# PET_Diag_Clip.net
KiCad netlist of a schematic drawn in EAGLE
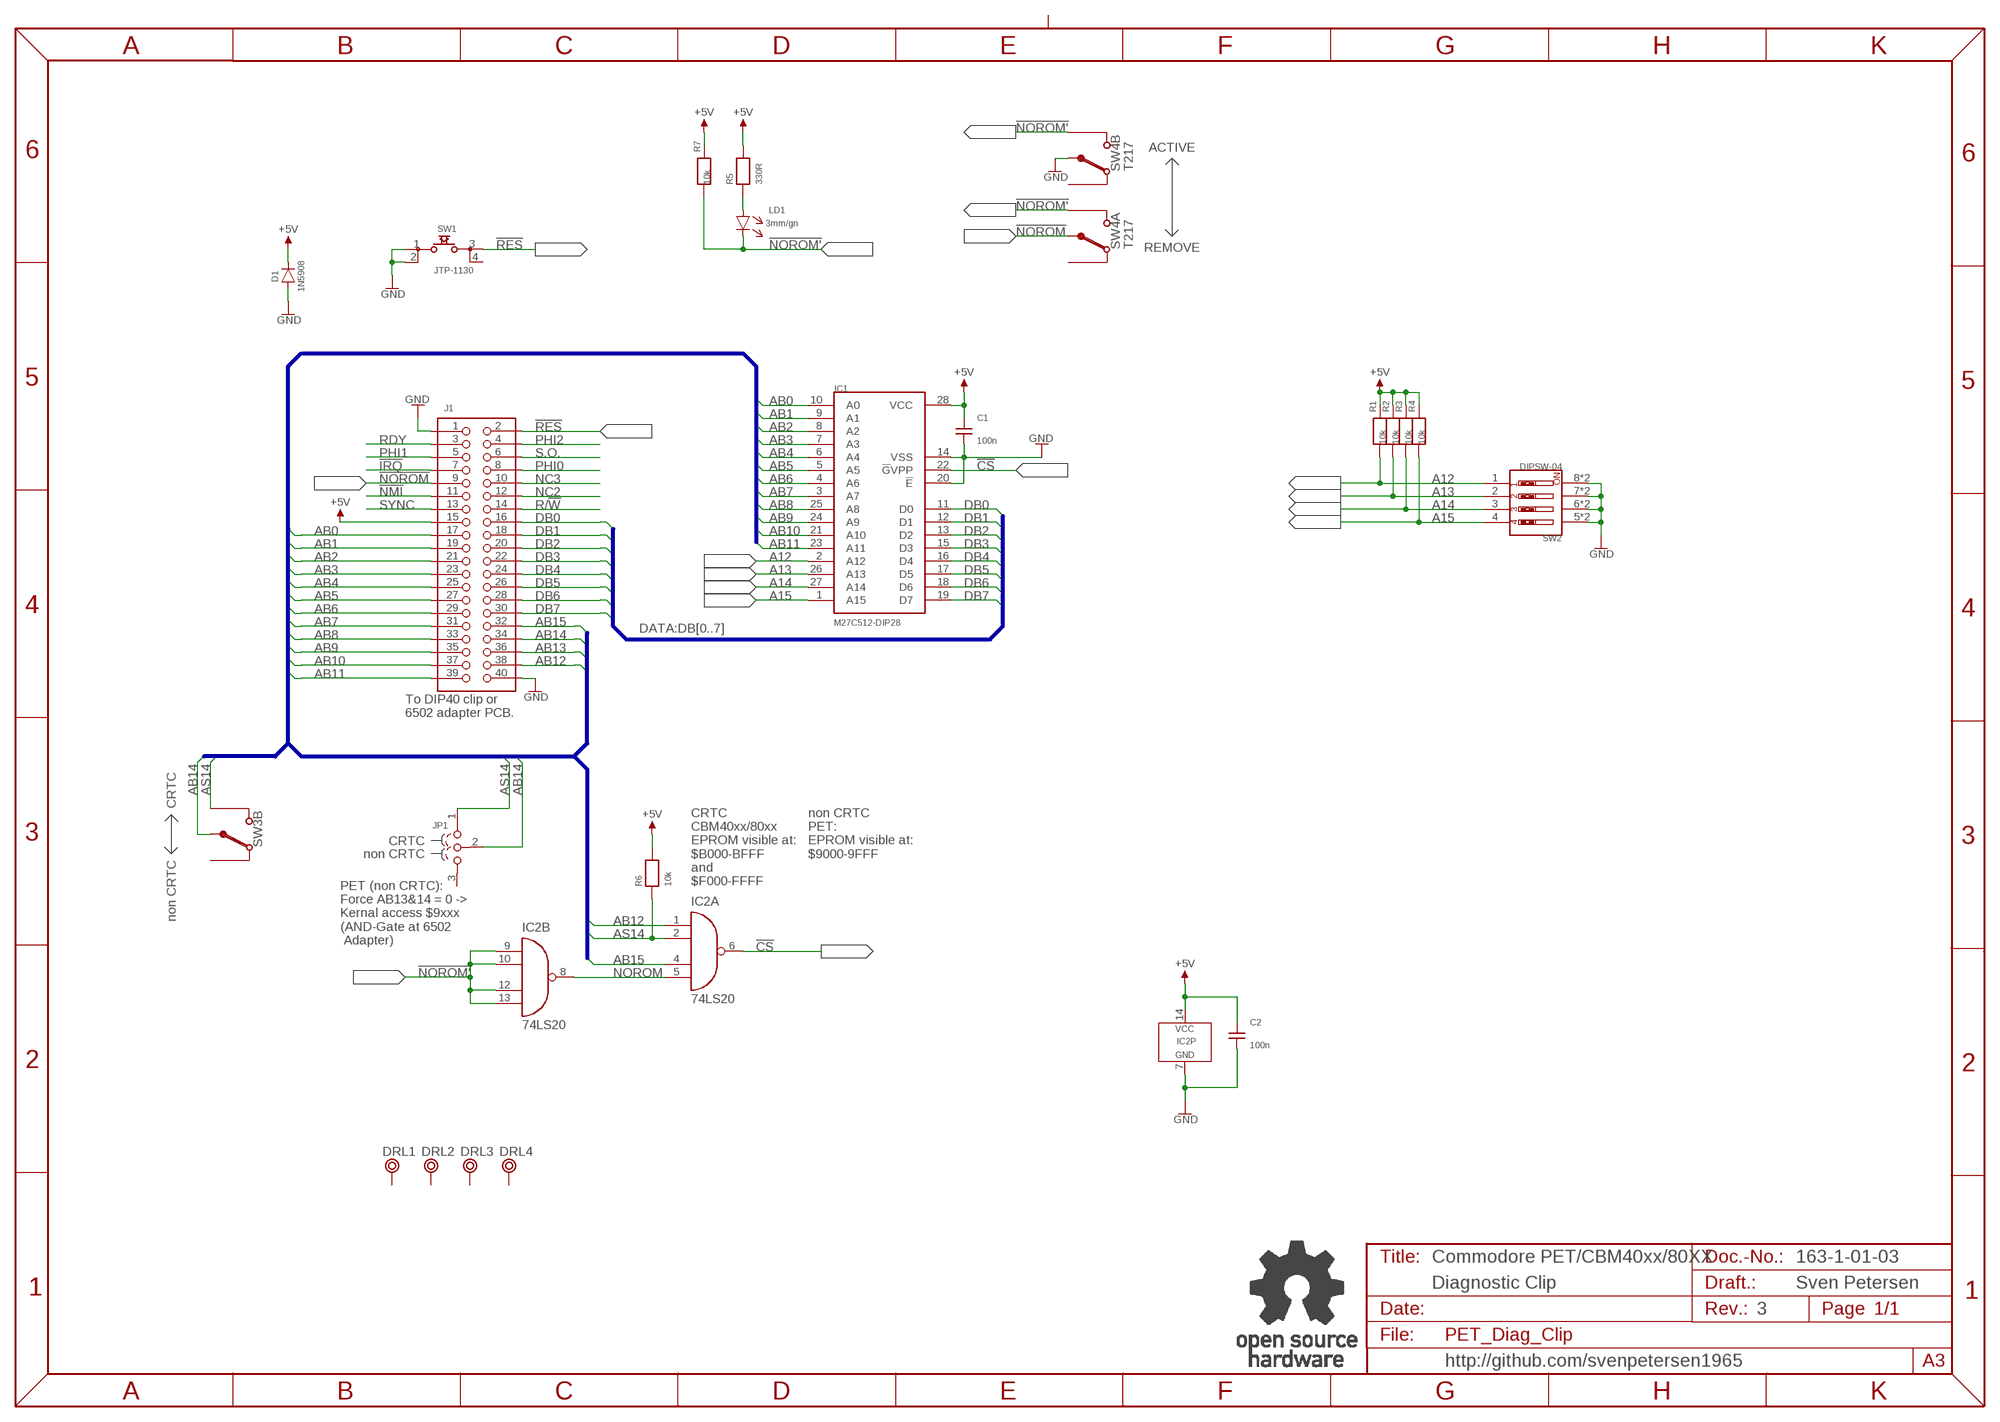
[diagram p0: schematic, sheet 1]

(export (version "E")
  (design (tool "Eeschema 10.0.6"))
  (components
    (comp (ref "C1")
      (value "100n")
      (footprint "eagle-import:C-2,5")
      (libsource (lib "eagle-import") (part "CAP01"))
    )
    (comp (ref "C2")
      (value "100n")
      (footprint "eagle-import:C-2,5")
      (libsource (lib "eagle-import") (part "CAP01"))
    )
    (comp (ref "D1")
      (value "1N5908")
      (footprint "eagle-import:DO-201")
      (libsource (lib "eagle-import") (part "1N5402"))
    )
    (comp (ref "DRL1")
      (value "BOHR3,5")
      (footprint "eagle-import:BOHR3,5")
      (libsource (lib "eagle-import") (part "BOHR3,5"))
    )
    (comp (ref "DRL2")
      (value "BOHR3,5")
      (footprint "eagle-import:BOHR3,5")
      (libsource (lib "eagle-import") (part "BOHR3,5"))
    )
    (comp (ref "DRL3")
      (value "BOHR3,5")
      (footprint "eagle-import:BOHR3,5")
      (libsource (lib "eagle-import") (part "BOHR3,5"))
    )
    (comp (ref "DRL4")
      (value "BOHR3,5")
      (footprint "eagle-import:BOHR3,5")
      (libsource (lib "eagle-import") (part "BOHR3,5"))
    )
    (comp (ref "IC1")
      (value "M27C512-DIP28")
      (footprint "eagle-import:DIL28-6")
      (libsource (lib "eagle-import") (part "M27C512-DIP28"))
    )
    (comp (ref "IC2")
      (value "74LS20")
      (footprint "eagle-import:DIL-14")
      (libsource (lib "eagle-import") (part "7420N"))
    )
    (comp (ref "J1")
      (value "PINHD-2X20WV")
      (footprint "eagle-import:2X20WV")
      (libsource (lib "eagle-import") (part "PINHD-2X20WV"))
    )
    (comp (ref "JP1")
      (value "COMBI-3P")
      (footprint "eagle-import:COMBI-3P")
      (libsource (lib "eagle-import") (part "COMBI-3P"))
    )
    (comp (ref "LD1")
      (value "3mm/gn")
      (footprint "eagle-import:3MM")
      (libsource (lib "eagle-import") (part "3MM"))
    )
    (comp (ref "R1")
      (value "10k")
      (footprint "eagle-import:R-10")
      (libsource (lib "eagle-import") (part "RES04"))
    )
    (comp (ref "R2")
      (value "10k")
      (footprint "eagle-import:R-10")
      (libsource (lib "eagle-import") (part "RES04"))
    )
    (comp (ref "R3")
      (value "10k")
      (footprint "eagle-import:R-10")
      (libsource (lib "eagle-import") (part "RES04"))
    )
    (comp (ref "R4")
      (value "10k")
      (footprint "eagle-import:R-10")
      (libsource (lib "eagle-import") (part "RES04"))
    )
    (comp (ref "R5")
      (value "330R")
      (footprint "eagle-import:R-10")
      (libsource (lib "eagle-import") (part "RES04"))
    )
    (comp (ref "R6")
      (value "10k")
      (footprint "eagle-import:R-10")
      (libsource (lib "eagle-import") (part "RES04"))
    )
    (comp (ref "R7")
      (value "10k")
      (footprint "eagle-import:R-10")
      (libsource (lib "eagle-import") (part "RES04"))
    )
    (comp (ref "SW1")
      (value "JTP-1130")
      (footprint "eagle-import:JTP-1130")
      (libsource (lib "eagle-import") (part "JTP-1130"))
    )
    (comp (ref "SW2")
      (value "DIPSW-04")
      (footprint "eagle-import:DIPSW-04V-COMBI")
      (libsource (lib "eagle-import") (part "DIPSW-04"))
    )
    (comp (ref "SW3")
      (value "MSS22D18")
      (footprint "eagle-import:DPDT_9MM")
      (libsource (lib "eagle-import") (part "DPDT_9MM"))
    )
    (comp (ref "SW4")
      (value "T217")
      (footprint "eagle-import:T217_SIDE")
      (libsource (lib "eagle-import") (part "T217"))
    )
    (comp (ref "U$13")
      (value "OPEN_SOURCE_HW")
      (footprint "eagle-import:OPENHW")
      (libsource (lib "eagle-import") (part "OPEN_SOURCE_HW"))
    )
  )
  (nets
    (net (code "9") (name "+5V") (class "Default")
      (node (ref "C1") (pin "2") (pinfunction "2_2") (pintype "passive"))
      (node (ref "C2") (pin "2") (pinfunction "2_2") (pintype "passive"))
      (node (ref "D1") (pin "K") (pinfunction "K_K") (pintype "passive"))
      (node (ref "IC1") (pin "28") (pinfunction "VCC_28") (pintype "power_in"))
      (node (ref "IC2") (pin "14") (pinfunction "VCC_14") (pintype "bidirectional"))
      (node (ref "J1") (pin "15") (pinfunction "15_15") (pintype "passive"))
      (node (ref "R1") (pin "1") (pinfunction "1_1") (pintype "passive"))
      (node (ref "R2") (pin "1") (pinfunction "1_1") (pintype "passive"))
      (node (ref "R3") (pin "1") (pinfunction "1_1") (pintype "passive"))
      (node (ref "R4") (pin "1") (pinfunction "1_1") (pintype "passive"))
      (node (ref "R5") (pin "2") (pinfunction "2_2") (pintype "passive"))
      (node (ref "R6") (pin "2") (pinfunction "2_2") (pintype "passive"))
      (node (ref "R7") (pin "1") (pinfunction "1_1") (pintype "passive"))
    )
    (net (code "10") (name "/A12") (class "Default")
      (node (ref "IC1") (pin "2") (pinfunction "A12_2") (pintype "input"))
      (node (ref "R1") (pin "2") (pinfunction "2_2") (pintype "passive"))
      (node (ref "SW2") (pin "1") (pinfunction "1_1") (pintype "passive"))
    )
    (net (code "11") (name "/A13") (class "Default")
      (node (ref "IC1") (pin "26") (pinfunction "A13_26") (pintype "input"))
      (node (ref "R2") (pin "2") (pinfunction "2_2") (pintype "passive"))
      (node (ref "SW2") (pin "2") (pinfunction "2_2") (pintype "passive"))
    )
    (net (code "12") (name "/A14") (class "Default")
      (node (ref "IC1") (pin "27") (pinfunction "A14_27") (pintype "input"))
      (node (ref "R3") (pin "2") (pinfunction "2_2") (pintype "passive"))
      (node (ref "SW2") (pin "3") (pinfunction "3_3") (pintype "passive"))
    )
    (net (code "13") (name "/A15") (class "Default")
      (node (ref "IC1") (pin "1") (pinfunction "A15_1") (pintype "input"))
      (node (ref "R4") (pin "2") (pinfunction "2_2") (pintype "passive"))
      (node (ref "SW2") (pin "4") (pinfunction "4_4") (pintype "passive"))
    )
    (net (code "14") (name "/AB0") (class "Default")
      (node (ref "IC1") (pin "10") (pinfunction "A0_10") (pintype "input"))
      (node (ref "J1") (pin "17") (pinfunction "17_17") (pintype "passive"))
    )
    (net (code "15") (name "/AB1") (class "Default")
      (node (ref "IC1") (pin "9") (pinfunction "A1_9") (pintype "input"))
      (node (ref "J1") (pin "19") (pinfunction "19_19") (pintype "passive"))
    )
    (net (code "16") (name "/AB2") (class "Default")
      (node (ref "IC1") (pin "8") (pinfunction "A2_8") (pintype "input"))
      (node (ref "J1") (pin "21") (pinfunction "21_21") (pintype "passive"))
    )
    (net (code "17") (name "/AB3") (class "Default")
      (node (ref "IC1") (pin "7") (pinfunction "A3_7") (pintype "input"))
      (node (ref "J1") (pin "23") (pinfunction "23_23") (pintype "passive"))
    )
    (net (code "18") (name "/AB4") (class "Default")
      (node (ref "IC1") (pin "6") (pinfunction "A4_6") (pintype "input"))
      (node (ref "J1") (pin "25") (pinfunction "25_25") (pintype "passive"))
    )
    (net (code "19") (name "/AB5") (class "Default")
      (node (ref "IC1") (pin "5") (pinfunction "A5_5") (pintype "input"))
      (node (ref "J1") (pin "27") (pinfunction "27_27") (pintype "passive"))
    )
    (net (code "20") (name "/AB6") (class "Default")
      (node (ref "IC1") (pin "4") (pinfunction "A6_4") (pintype "input"))
      (node (ref "J1") (pin "29") (pinfunction "29_29") (pintype "passive"))
    )
    (net (code "21") (name "/AB7") (class "Default")
      (node (ref "IC1") (pin "3") (pinfunction "A7_3") (pintype "input"))
      (node (ref "J1") (pin "31") (pinfunction "31_31") (pintype "passive"))
    )
    (net (code "22") (name "/AB8") (class "Default")
      (node (ref "IC1") (pin "25") (pinfunction "A8_25") (pintype "input"))
      (node (ref "J1") (pin "33") (pinfunction "33_33") (pintype "passive"))
    )
    (net (code "23") (name "/AB9") (class "Default")
      (node (ref "IC1") (pin "24") (pinfunction "A9_24") (pintype "input"))
      (node (ref "J1") (pin "35") (pinfunction "35_35") (pintype "passive"))
    )
    (net (code "24") (name "/AB10") (class "Default")
      (node (ref "IC1") (pin "21") (pinfunction "A10_21") (pintype "input"))
      (node (ref "J1") (pin "37") (pinfunction "37_37") (pintype "passive"))
    )
    (net (code "25") (name "/AB11") (class "Default")
      (node (ref "IC1") (pin "23") (pinfunction "A11_23") (pintype "input"))
      (node (ref "J1") (pin "39") (pinfunction "39_39") (pintype "passive"))
    )
    (net (code "26") (name "/AB12") (class "Default")
      (node (ref "IC2") (pin "1") (pinfunction "I0_1") (pintype "input"))
      (node (ref "J1") (pin "38") (pinfunction "38_38") (pintype "passive"))
    )
    (net (code "27") (name "/AB13") (class "Default")
      (node (ref "J1") (pin "36") (pinfunction "36_36") (pintype "passive"))
    )
    (net (code "28") (name "/AB14") (class "Default")
      (node (ref "J1") (pin "34") (pinfunction "34_34") (pintype "passive"))
      (node (ref "JP1") (pin "2") (pinfunction "2_2") (pintype "bidirectional"))
      (node (ref "SW3") (pin "5") (pinfunction "COM_5") (pintype "bidirectional"))
    )
    (net (code "29") (name "/AB15") (class "Default")
      (node (ref "IC2") (pin "4") (pinfunction "I2_4") (pintype "input"))
      (node (ref "J1") (pin "32") (pinfunction "32_32") (pintype "passive"))
    )
    (net (code "30") (name "/AS14") (class "Default")
      (node (ref "IC2") (pin "2") (pinfunction "I1_2") (pintype "input"))
      (node (ref "JP1") (pin "1") (pinfunction "1_1") (pintype "bidirectional"))
      (node (ref "R6") (pin "1") (pinfunction "1_1") (pintype "passive"))
      (node (ref "SW3") (pin "6") (pinfunction "UP_6") (pintype "bidirectional"))
    )
    (net (code "32") (name "/DB0") (class "Default")
      (node (ref "IC1") (pin "11") (pinfunction "D0_11") (pintype "bidirectional"))
      (node (ref "J1") (pin "16") (pinfunction "16_16") (pintype "passive"))
    )
    (net (code "33") (name "/DB1") (class "Default")
      (node (ref "IC1") (pin "12") (pinfunction "D1_12") (pintype "bidirectional"))
      (node (ref "J1") (pin "18") (pinfunction "18_18") (pintype "passive"))
    )
    (net (code "34") (name "/DB2") (class "Default")
      (node (ref "IC1") (pin "13") (pinfunction "D2_13") (pintype "bidirectional"))
      (node (ref "J1") (pin "20") (pinfunction "20_20") (pintype "passive"))
    )
    (net (code "35") (name "/DB3") (class "Default")
      (node (ref "IC1") (pin "15") (pinfunction "D3_15") (pintype "bidirectional"))
      (node (ref "J1") (pin "22") (pinfunction "22_22") (pintype "passive"))
    )
    (net (code "36") (name "/DB4") (class "Default")
      (node (ref "IC1") (pin "16") (pinfunction "D4_16") (pintype "bidirectional"))
      (node (ref "J1") (pin "24") (pinfunction "24_24") (pintype "passive"))
    )
    (net (code "37") (name "/DB5") (class "Default")
      (node (ref "IC1") (pin "17") (pinfunction "D5_17") (pintype "bidirectional"))
      (node (ref "J1") (pin "26") (pinfunction "26_26") (pintype "passive"))
    )
    (net (code "38") (name "/DB6") (class "Default")
      (node (ref "IC1") (pin "18") (pinfunction "D6_18") (pintype "bidirectional"))
      (node (ref "J1") (pin "28") (pinfunction "28_28") (pintype "passive"))
    )
    (net (code "39") (name "/DB7") (class "Default")
      (node (ref "IC1") (pin "19") (pinfunction "D7_19") (pintype "bidirectional"))
      (node (ref "J1") (pin "30") (pinfunction "30_30") (pintype "passive"))
    )
    (net (code "40") (name "/NC2") (class "Default")
      (node (ref "J1") (pin "12") (pinfunction "12_12") (pintype "passive"))
    )
    (net (code "41") (name "/NC3") (class "Default")
      (node (ref "J1") (pin "10") (pinfunction "10_10") (pintype "passive"))
    )
    (net (code "42") (name "/NOROM") (class "Default")
      (node (ref "IC2") (pin "5") (pinfunction "I3_5") (pintype "input"))
      (node (ref "IC2") (pin "8") (pinfunction "O_8") (pintype "output"))
    )
    (net (code "43") (name "/PHI0") (class "Default")
      (node (ref "J1") (pin "8") (pinfunction "8_8") (pintype "passive"))
    )
    (net (code "44") (name "/PHI1") (class "Default")
      (node (ref "J1") (pin "5") (pinfunction "5_5") (pintype "passive"))
    )
    (net (code "45") (name "/PHI2") (class "Default")
      (node (ref "J1") (pin "4") (pinfunction "4_4") (pintype "passive"))
    )
    (net (code "46") (name "/RDY") (class "Default")
      (node (ref "J1") (pin "3") (pinfunction "3_3") (pintype "passive"))
    )
    (net (code "47") (name "/R{slash}~{W}") (class "Default")
      (node (ref "J1") (pin "14") (pinfunction "14_14") (pintype "passive"))
    )
    (net (code "48") (name "/S.O.") (class "Default")
      (node (ref "J1") (pin "6") (pinfunction "6_6") (pintype "passive"))
    )
    (net (code "49") (name "/SYNC") (class "Default")
      (node (ref "J1") (pin "13") (pinfunction "13_13") (pintype "passive"))
    )
    (net (code "50") (name "/~{CS}") (class "Default")
      (node (ref "IC1") (pin "22") (pinfunction "~{G}VPP_22") (pintype "input"))
      (node (ref "IC2") (pin "6") (pinfunction "O_6") (pintype "output"))
    )
    (net (code "51") (name "/~{IRQ}") (class "Default")
      (node (ref "J1") (pin "7") (pinfunction "7_7") (pintype "passive"))
    )
    (net (code "52") (name "/~{NMI}") (class "Default")
      (node (ref "J1") (pin "11") (pinfunction "11_11") (pintype "passive"))
    )
    (net (code "53") (name "/~{NOROM'}") (class "Default")
      (node (ref "IC2") (pin "10") (pinfunction "I1_10") (pintype "input"))
      (node (ref "IC2") (pin "12") (pinfunction "I2_12") (pintype "input"))
      (node (ref "IC2") (pin "13") (pinfunction "I3_13") (pintype "input"))
      (node (ref "IC2") (pin "9") (pinfunction "I0_9") (pintype "input"))
      (node (ref "LD1") (pin "C") (pinfunction "K_C") (pintype "bidirectional"))
      (node (ref "R7") (pin "2") (pinfunction "2_2") (pintype "passive"))
      (node (ref "SW4") (pin "UP1") (pinfunction "UP_UP1") (pintype "bidirectional"))
      (node (ref "SW4") (pin "UP2") (pinfunction "UP_UP2") (pintype "bidirectional"))
    )
    (net (code "54") (name "/~{NOROM}") (class "Default")
      (node (ref "J1") (pin "9") (pinfunction "9_9") (pintype "passive"))
      (node (ref "SW4") (pin "COM1") (pinfunction "COM_COM1") (pintype "bidirectional"))
    )
    (net (code "55") (name "/~{RES}") (class "Default")
      (node (ref "J1") (pin "2") (pinfunction "2_2") (pintype "passive"))
      (node (ref "SW1") (pin "3") (pinfunction "3_3") (pintype "passive"))
    )
    (net (code "56") (name "GND") (class "Default")
      (node (ref "C1") (pin "1") (pinfunction "1_1") (pintype "passive"))
      (node (ref "C2") (pin "1") (pinfunction "1_1") (pintype "passive"))
      (node (ref "D1") (pin "A") (pinfunction "A_A") (pintype "passive"))
      (node (ref "IC1") (pin "14") (pinfunction "VSS_14") (pintype "power_in"))
      (node (ref "IC1") (pin "20") (pinfunction "~{E}_20") (pintype "input"))
      (node (ref "IC2") (pin "7") (pinfunction "GND_7") (pintype "bidirectional"))
      (node (ref "J1") (pin "1") (pinfunction "1_1") (pintype "passive"))
      (node (ref "J1") (pin "40") (pinfunction "40_40") (pintype "passive"))
      (node (ref "SW1") (pin "1") (pinfunction "1_1") (pintype "passive"))
      (node (ref "SW1") (pin "2") (pinfunction "2_2") (pintype "passive"))
      (node (ref "SW2") (pin "5") (pinfunction "5_5") (pintype "passive"))
      (node (ref "SW2") (pin "5A") (pinfunction "5_5A") (pintype "passive"))
      (node (ref "SW2") (pin "6") (pinfunction "6_6") (pintype "passive"))
      (node (ref "SW2") (pin "6A") (pinfunction "6_6A") (pintype "passive"))
      (node (ref "SW2") (pin "7") (pinfunction "7_7") (pintype "passive"))
      (node (ref "SW2") (pin "7A") (pinfunction "7_7A") (pintype "passive"))
      (node (ref "SW2") (pin "8") (pinfunction "8_8") (pintype "passive"))
      (node (ref "SW2") (pin "8A") (pinfunction "8_8A") (pintype "passive"))
      (node (ref "SW4") (pin "COM2") (pinfunction "COM_COM2") (pintype "bidirectional"))
    )
    (net (code "57") (name "Net-(LD1-PadA)") (class "Default")
      (node (ref "LD1") (pin "A") (pinfunction "A_A") (pintype "bidirectional"))
      (node (ref "R5") (pin "1") (pinfunction "1_1") (pintype "passive"))
    )
    (net (code "58") (name "unconnected-(DRL1-PadP$1)") (class "Default")
      (node (ref "DRL1") (pin "P$1") (pinfunction "P$1_P$1") (pintype "passive"))
    )
    (net (code "59") (name "unconnected-(DRL2-PadP$1)") (class "Default")
      (node (ref "DRL2") (pin "P$1") (pinfunction "P$1_P$1") (pintype "passive"))
    )
    (net (code "60") (name "unconnected-(DRL3-PadP$1)") (class "Default")
      (node (ref "DRL3") (pin "P$1") (pinfunction "P$1_P$1") (pintype "passive"))
    )
    (net (code "61") (name "unconnected-(DRL4-PadP$1)") (class "Default")
      (node (ref "DRL4") (pin "P$1") (pinfunction "P$1_P$1") (pintype "passive"))
    )
    (net (code "62") (name "unconnected-(JP1-Pad3)") (class "Default")
      (node (ref "JP1") (pin "3") (pinfunction "3_3") (pintype "bidirectional"))
    )
    (net (code "63") (name "unconnected-(SW1-Pad4)") (class "Default")
      (node (ref "SW1") (pin "4") (pinfunction "4_4") (pintype "passive"))
    )
    (net (code "64") (name "unconnected-(SW3B-DWN-Pad4)") (class "Default")
      (node (ref "SW3") (pin "4") (pinfunction "DWN_4") (pintype "bidirectional"))
    )
    (net (code "65") (name "unconnected-(SW4A-DWN-PadDWN1)") (class "Default")
      (node (ref "SW4") (pin "DWN1") (pinfunction "DWN_DWN1") (pintype "bidirectional"))
    )
    (net (code "66") (name "unconnected-(SW4B-DWN-PadDWN2)") (class "Default")
      (node (ref "SW4") (pin "DWN2") (pinfunction "DWN_DWN2") (pintype "bidirectional"))
    )
  )
)
